# Top.net
KiCad netlist of a schematic drawn in Altium Designer
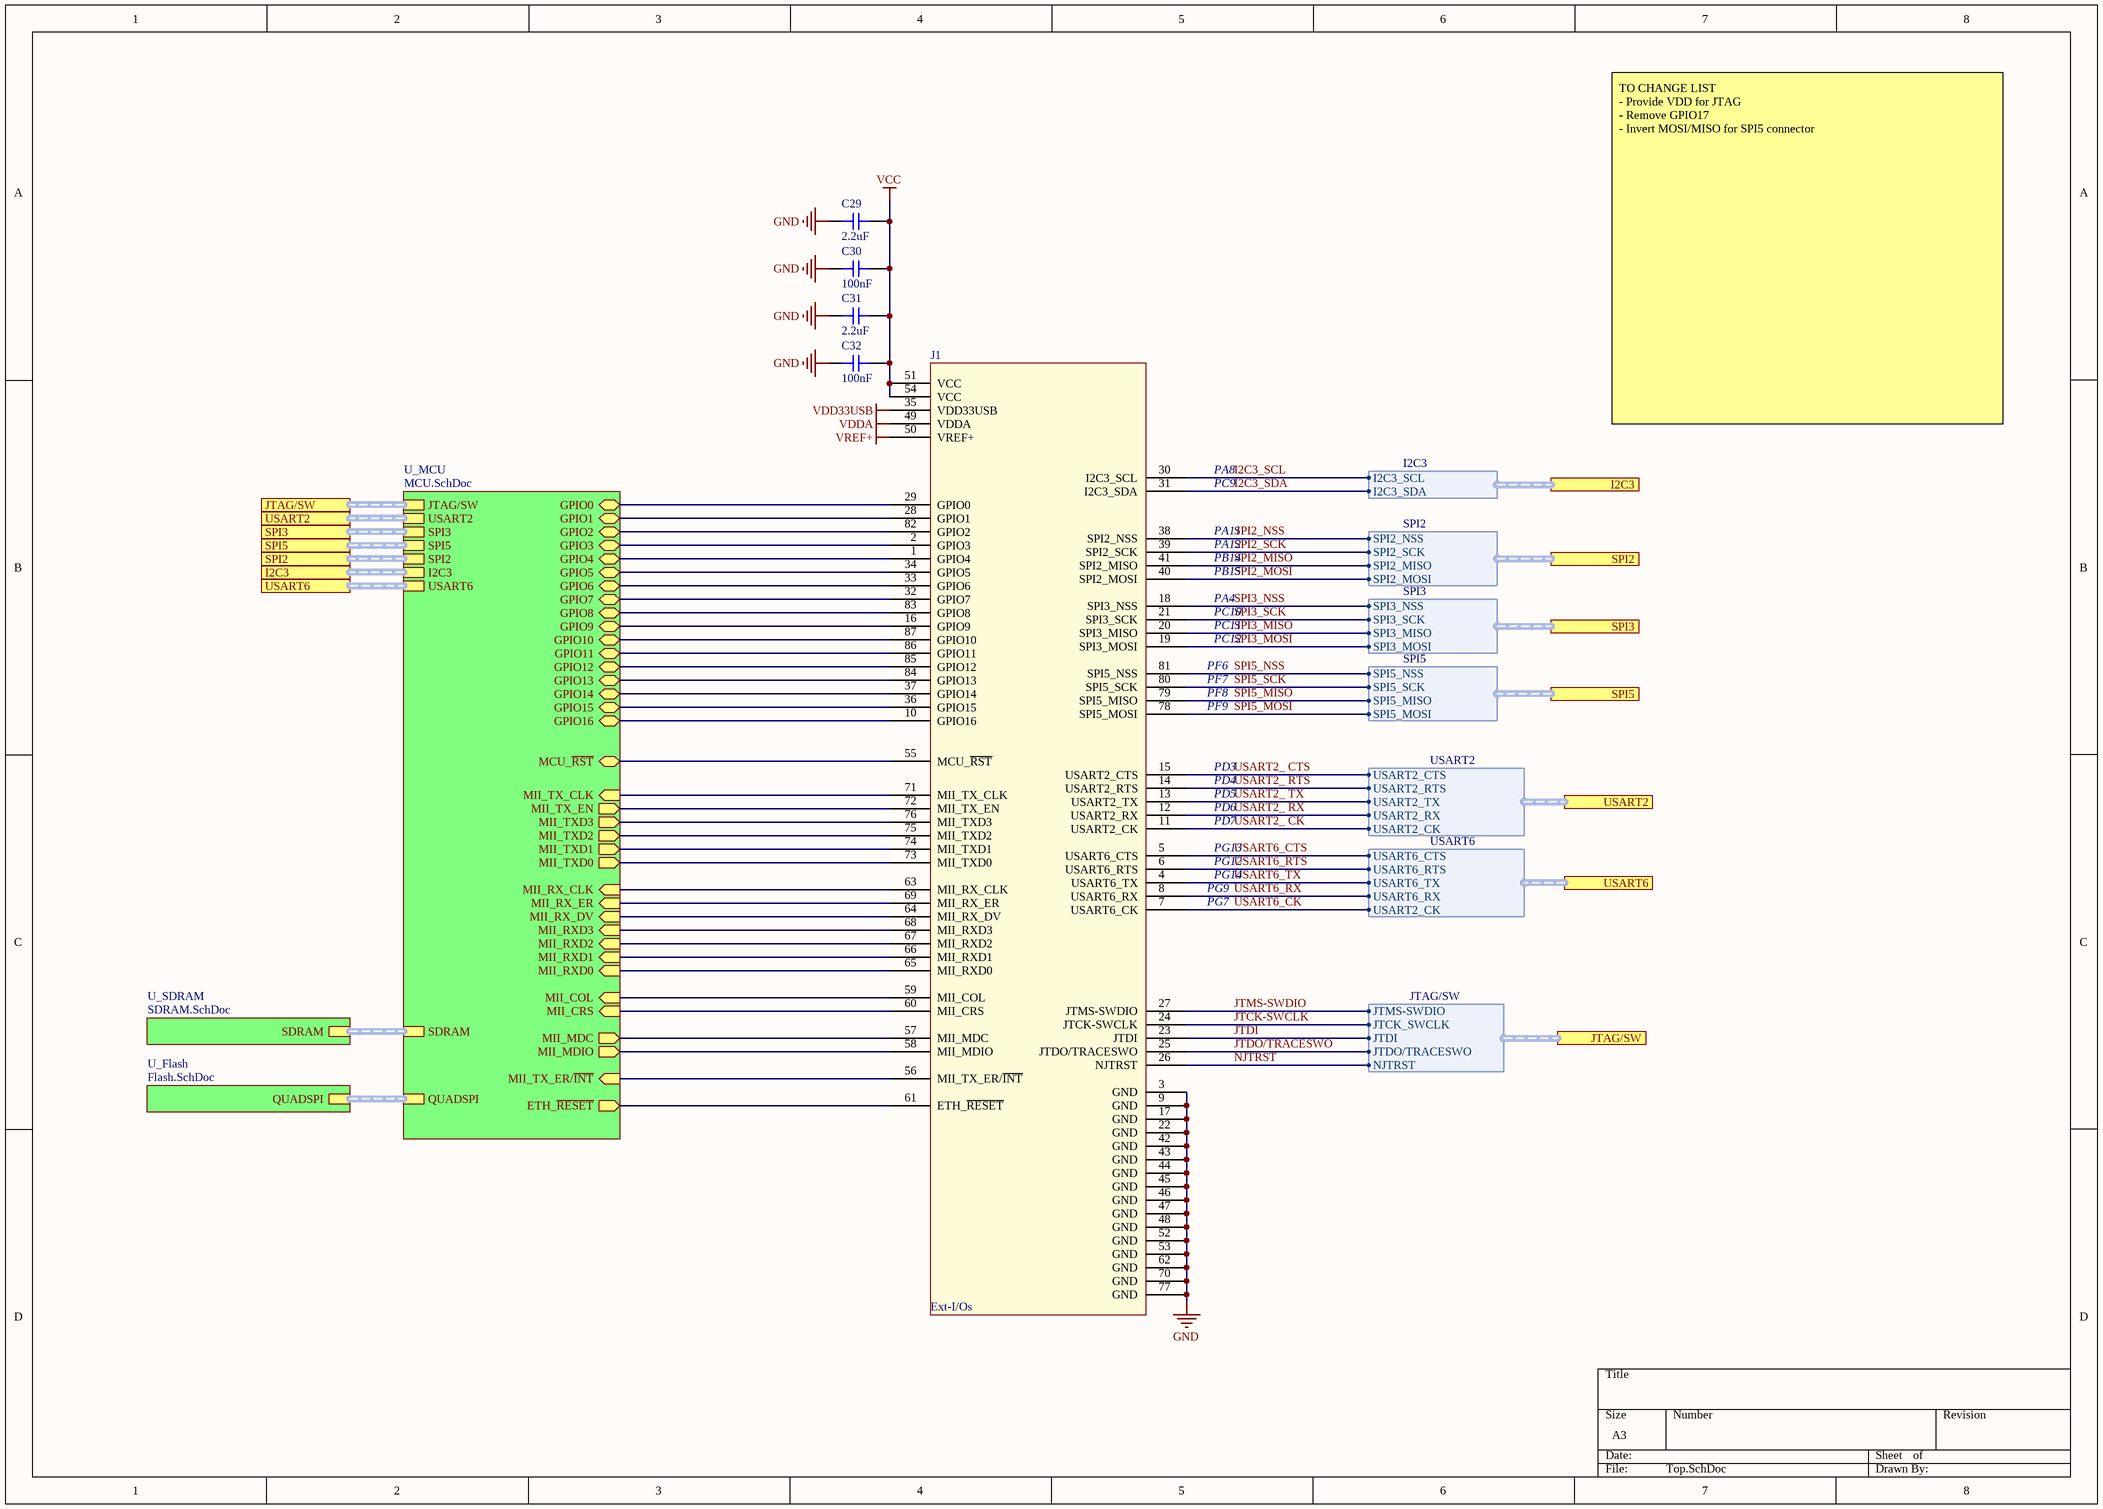
[diagram p0: Top.SchDoc]

(export (version "E")
  (design (tool "Eeschema 10.0.6"))
  (components
    (comp (ref "C29")
      (value "2.2uF")
      (footprint "Capacitor-0603")
      (fields (field (name "Comment") "C-2.2uF-0603"))
      (libsource (lib "Components") (part "C-2.2uF-0603"))
    )
    (comp (ref "C30")
      (value "100nF")
      (footprint "Capacitor-0603")
      (fields (field (name "Comment") "C-100nF-0603"))
      (libsource (lib "Components") (part "C-100nF-0603"))
    )
    (comp (ref "C31")
      (value "2.2uF")
      (footprint "Capacitor-0603")
      (fields (field (name "Comment") "C-2.2uF-0603"))
      (libsource (lib "Components") (part "C-2.2uF-0603"))
    )
    (comp (ref "C32")
      (value "100nF")
      (footprint "Capacitor-0603")
      (fields (field (name "Comment") "C-100nF-0603"))
      (libsource (lib "Components") (part "C-100nF-0603"))
    )
    (comp (ref "J1")
      (value "Ext-I/Os")
      (footprint "EXT_IOS")
      (libsource (lib "Components") (part "Ext-I/Os"))
    )
  )
  (nets
    (net (code "8") (name "/ETH_~{RESET}") (class "Default")
      (node (ref "J1") (pin "61") (pinfunction "ETH_~{RESET}_61") (pintype "passive"))
    )
    (net (code "9") (name "/GPIO0") (class "Default")
      (node (ref "J1") (pin "29") (pinfunction "GPIO0_29") (pintype "passive"))
    )
    (net (code "10") (name "/GPIO1") (class "Default")
      (node (ref "J1") (pin "28") (pinfunction "GPIO1_28") (pintype "passive"))
    )
    (net (code "11") (name "/GPIO2") (class "Default")
      (node (ref "J1") (pin "82") (pinfunction "GPIO2_82") (pintype "passive"))
    )
    (net (code "12") (name "/GPIO3") (class "Default")
      (node (ref "J1") (pin "2") (pinfunction "GPIO3_2") (pintype "passive"))
    )
    (net (code "13") (name "/GPIO4") (class "Default")
      (node (ref "J1") (pin "1") (pinfunction "GPIO4_1") (pintype "passive"))
    )
    (net (code "14") (name "/GPIO5") (class "Default")
      (node (ref "J1") (pin "34") (pinfunction "GPIO5_34") (pintype "passive"))
    )
    (net (code "15") (name "/GPIO6") (class "Default")
      (node (ref "J1") (pin "33") (pinfunction "GPIO6_33") (pintype "passive"))
    )
    (net (code "16") (name "/GPIO7") (class "Default")
      (node (ref "J1") (pin "32") (pinfunction "GPIO7_32") (pintype "passive"))
    )
    (net (code "17") (name "/GPIO8") (class "Default")
      (node (ref "J1") (pin "83") (pinfunction "GPIO8_83") (pintype "passive"))
    )
    (net (code "18") (name "/GPIO9") (class "Default")
      (node (ref "J1") (pin "16") (pinfunction "GPIO9_16") (pintype "passive"))
    )
    (net (code "19") (name "/GPIO10") (class "Default")
      (node (ref "J1") (pin "87") (pinfunction "GPIO10_87") (pintype "passive"))
    )
    (net (code "20") (name "/GPIO11") (class "Default")
      (node (ref "J1") (pin "86") (pinfunction "GPIO11_86") (pintype "passive"))
    )
    (net (code "21") (name "/GPIO12") (class "Default")
      (node (ref "J1") (pin "85") (pinfunction "GPIO12_85") (pintype "passive"))
    )
    (net (code "22") (name "/GPIO13") (class "Default")
      (node (ref "J1") (pin "84") (pinfunction "GPIO13_84") (pintype "passive"))
    )
    (net (code "23") (name "/GPIO14") (class "Default")
      (node (ref "J1") (pin "37") (pinfunction "GPIO14_37") (pintype "passive"))
    )
    (net (code "24") (name "/GPIO15") (class "Default")
      (node (ref "J1") (pin "36") (pinfunction "GPIO15_36") (pintype "passive"))
    )
    (net (code "25") (name "/GPIO16") (class "Default")
      (node (ref "J1") (pin "10") (pinfunction "GPIO16_10") (pintype "passive"))
    )
    (net (code "26") (name "/I2C3_SCL") (class "Default")
      (node (ref "J1") (pin "30") (pinfunction "I2C3_SCL_30") (pintype "passive"))
    )
    (net (code "27") (name "/I2C3_SDA") (class "Default")
      (node (ref "J1") (pin "31") (pinfunction "I2C3_SDA_31") (pintype "passive"))
    )
    (net (code "28") (name "/JTCK-SWCLK") (class "Default")
      (node (ref "J1") (pin "24") (pinfunction "JTCK-SWCLK_24") (pintype "passive"))
    )
    (net (code "29") (name "/JTDI") (class "Default")
      (node (ref "J1") (pin "23") (pinfunction "JTDI_23") (pintype "passive"))
    )
    (net (code "30") (name "/JTDO{slash}TRACESWO") (class "Default")
      (node (ref "J1") (pin "25") (pinfunction "JTDO/TRACESWO_25") (pintype "passive"))
    )
    (net (code "31") (name "/JTMS-SWDIO") (class "Default")
      (node (ref "J1") (pin "27") (pinfunction "JTMS-SWDIO_27") (pintype "passive"))
    )
    (net (code "32") (name "/MCU_~{RST}") (class "Default")
      (node (ref "J1") (pin "55") (pinfunction "MCU_~{RST}_55") (pintype "passive"))
    )
    (net (code "33") (name "/MII_COL") (class "Default")
      (node (ref "J1") (pin "59") (pinfunction "MII_COL_59") (pintype "passive"))
    )
    (net (code "34") (name "/MII_CRS") (class "Default")
      (node (ref "J1") (pin "60") (pinfunction "MII_CRS_60") (pintype "passive"))
    )
    (net (code "35") (name "/MII_MDC") (class "Default")
      (node (ref "J1") (pin "57") (pinfunction "MII_MDC_57") (pintype "passive"))
    )
    (net (code "36") (name "/MII_MDIO") (class "Default")
      (node (ref "J1") (pin "58") (pinfunction "MII_MDIO_58") (pintype "passive"))
    )
    (net (code "37") (name "/MII_RXD0") (class "Default")
      (node (ref "J1") (pin "65") (pinfunction "MII_RXD0_65") (pintype "passive"))
    )
    (net (code "38") (name "/MII_RXD1") (class "Default")
      (node (ref "J1") (pin "66") (pinfunction "MII_RXD1_66") (pintype "passive"))
    )
    (net (code "39") (name "/MII_RXD2") (class "Default")
      (node (ref "J1") (pin "67") (pinfunction "MII_RXD2_67") (pintype "passive"))
    )
    (net (code "40") (name "/MII_RXD3") (class "Default")
      (node (ref "J1") (pin "68") (pinfunction "MII_RXD3_68") (pintype "passive"))
    )
    (net (code "41") (name "/MII_RX_CLK") (class "Default")
      (node (ref "J1") (pin "63") (pinfunction "MII_RX_CLK_63") (pintype "passive"))
    )
    (net (code "42") (name "/MII_RX_DV") (class "Default")
      (node (ref "J1") (pin "64") (pinfunction "MII_RX_DV_64") (pintype "passive"))
    )
    (net (code "43") (name "/MII_RX_ER") (class "Default")
      (node (ref "J1") (pin "69") (pinfunction "MII_RX_ER_69") (pintype "passive"))
    )
    (net (code "44") (name "/MII_TXD0") (class "Default")
      (node (ref "J1") (pin "73") (pinfunction "MII_TXD0_73") (pintype "passive"))
    )
    (net (code "45") (name "/MII_TXD1") (class "Default")
      (node (ref "J1") (pin "74") (pinfunction "MII_TXD1_74") (pintype "passive"))
    )
    (net (code "46") (name "/MII_TXD2") (class "Default")
      (node (ref "J1") (pin "75") (pinfunction "MII_TXD2_75") (pintype "passive"))
    )
    (net (code "47") (name "/MII_TXD3") (class "Default")
      (node (ref "J1") (pin "76") (pinfunction "MII_TXD3_76") (pintype "passive"))
    )
    (net (code "48") (name "/MII_TX_CLK") (class "Default")
      (node (ref "J1") (pin "71") (pinfunction "MII_TX_CLK_71") (pintype "passive"))
    )
    (net (code "49") (name "/MII_TX_EN") (class "Default")
      (node (ref "J1") (pin "72") (pinfunction "MII_TX_EN_72") (pintype "passive"))
    )
    (net (code "50") (name "/MII_TX_ER{slash}~{INT}") (class "Default")
      (node (ref "J1") (pin "56") (pinfunction "MII_TX_ER/~{INT}_56") (pintype "passive"))
    )
    (net (code "51") (name "/NJTRST") (class "Default")
      (node (ref "J1") (pin "26") (pinfunction "NJTRST_26") (pintype "passive"))
    )
    (net (code "54") (name "/SPI2_MISO") (class "Default")
      (node (ref "J1") (pin "41") (pinfunction "SPI2_MISO_41") (pintype "passive"))
    )
    (net (code "55") (name "/SPI2_MOSI") (class "Default")
      (node (ref "J1") (pin "40") (pinfunction "SPI2_MOSI_40") (pintype "passive"))
    )
    (net (code "56") (name "/SPI2_NSS") (class "Default")
      (node (ref "J1") (pin "38") (pinfunction "SPI2_NSS_38") (pintype "passive"))
    )
    (net (code "57") (name "/SPI2_SCK") (class "Default")
      (node (ref "J1") (pin "39") (pinfunction "SPI2_SCK_39") (pintype "passive"))
    )
    (net (code "58") (name "/SPI3_MISO") (class "Default")
      (node (ref "J1") (pin "20") (pinfunction "SPI3_MISO_20") (pintype "passive"))
    )
    (net (code "59") (name "/SPI3_MOSI") (class "Default")
      (node (ref "J1") (pin "19") (pinfunction "SPI3_MOSI_19") (pintype "passive"))
    )
    (net (code "60") (name "/SPI3_NSS") (class "Default")
      (node (ref "J1") (pin "18") (pinfunction "SPI3_NSS_18") (pintype "passive"))
    )
    (net (code "61") (name "/SPI3_SCK") (class "Default")
      (node (ref "J1") (pin "21") (pinfunction "SPI3_SCK_21") (pintype "passive"))
    )
    (net (code "62") (name "/SPI5_MISO") (class "Default")
      (node (ref "J1") (pin "79") (pinfunction "SPI5_MISO_79") (pintype "passive"))
    )
    (net (code "63") (name "/SPI5_MOSI") (class "Default")
      (node (ref "J1") (pin "78") (pinfunction "SPI5_MOSI_78") (pintype "passive"))
    )
    (net (code "64") (name "/SPI5_NSS") (class "Default")
      (node (ref "J1") (pin "81") (pinfunction "SPI5_NSS_81") (pintype "passive"))
    )
    (net (code "65") (name "/SPI5_SCK") (class "Default")
      (node (ref "J1") (pin "80") (pinfunction "SPI5_SCK_80") (pintype "passive"))
    )
    (net (code "66") (name "/USART2_ CK") (class "Default")
      (node (ref "J1") (pin "11") (pinfunction "USART2_CK_11") (pintype "passive"))
    )
    (net (code "67") (name "/USART2_ CTS") (class "Default")
      (node (ref "J1") (pin "15") (pinfunction "USART2_CTS_15") (pintype "passive"))
    )
    (net (code "68") (name "/USART2_ RTS") (class "Default")
      (node (ref "J1") (pin "14") (pinfunction "USART2_RTS_14") (pintype "passive"))
    )
    (net (code "69") (name "/USART2_ RX") (class "Default")
      (node (ref "J1") (pin "12") (pinfunction "USART2_RX_12") (pintype "passive"))
    )
    (net (code "70") (name "/USART2_ TX") (class "Default")
      (node (ref "J1") (pin "13") (pinfunction "USART2_TX_13") (pintype "passive"))
    )
    (net (code "71") (name "/USART6_CK") (class "Default")
      (node (ref "J1") (pin "7") (pinfunction "USART6_CK_7") (pintype "passive"))
    )
    (net (code "72") (name "/USART6_CTS") (class "Default")
      (node (ref "J1") (pin "5") (pinfunction "USART6_CTS_5") (pintype "passive"))
    )
    (net (code "73") (name "/USART6_RTS") (class "Default")
      (node (ref "J1") (pin "6") (pinfunction "USART6_RTS_6") (pintype "passive"))
    )
    (net (code "74") (name "/USART6_RX") (class "Default")
      (node (ref "J1") (pin "8") (pinfunction "USART6_RX_8") (pintype "passive"))
    )
    (net (code "75") (name "/USART6_TX") (class "Default")
      (node (ref "J1") (pin "4") (pinfunction "USART6_TX_4") (pintype "passive"))
    )
    (net (code "83") (name "GND") (class "Default")
      (node (ref "C29") (pin "1") (pinfunction "1_1") (pintype "passive"))
      (node (ref "C30") (pin "1") (pinfunction "1_1") (pintype "passive"))
      (node (ref "C31") (pin "1") (pinfunction "1_1") (pintype "passive"))
      (node (ref "C32") (pin "1") (pinfunction "1_1") (pintype "passive"))
      (node (ref "J1") (pin "17") (pinfunction "GND_17") (pintype "passive"))
      (node (ref "J1") (pin "22") (pinfunction "GND_22") (pintype "passive"))
      (node (ref "J1") (pin "3") (pinfunction "GND_3") (pintype "passive"))
      (node (ref "J1") (pin "42") (pinfunction "GND_42") (pintype "passive"))
      (node (ref "J1") (pin "43") (pinfunction "GND_43") (pintype "passive"))
      (node (ref "J1") (pin "44") (pinfunction "GND_44") (pintype "passive"))
      (node (ref "J1") (pin "45") (pinfunction "GND_45") (pintype "passive"))
      (node (ref "J1") (pin "46") (pinfunction "GND_46") (pintype "passive"))
      (node (ref "J1") (pin "47") (pinfunction "GND_47") (pintype "passive"))
      (node (ref "J1") (pin "48") (pinfunction "GND_48") (pintype "passive"))
      (node (ref "J1") (pin "52") (pinfunction "GND_52") (pintype "passive"))
      (node (ref "J1") (pin "53") (pinfunction "GND_53") (pintype "passive"))
      (node (ref "J1") (pin "62") (pinfunction "GND_62") (pintype "passive"))
      (node (ref "J1") (pin "70") (pinfunction "GND_70") (pintype "passive"))
      (node (ref "J1") (pin "77") (pinfunction "GND_77") (pintype "passive"))
      (node (ref "J1") (pin "9") (pinfunction "GND_9") (pintype "passive"))
    )
    (net (code "84") (name "VCC") (class "Default")
      (node (ref "C29") (pin "2") (pinfunction "2_2") (pintype "passive"))
      (node (ref "C30") (pin "2") (pinfunction "2_2") (pintype "passive"))
      (node (ref "C31") (pin "2") (pinfunction "2_2") (pintype "passive"))
      (node (ref "C32") (pin "2") (pinfunction "2_2") (pintype "passive"))
      (node (ref "J1") (pin "51") (pinfunction "VCC_51") (pintype "passive"))
      (node (ref "J1") (pin "54") (pinfunction "VCC_54") (pintype "passive"))
    )
    (net (code "85") (name "VDD33USB") (class "Default")
      (node (ref "J1") (pin "35") (pinfunction "VDD33USB_35") (pintype "passive"))
    )
    (net (code "86") (name "VDDA") (class "Default")
      (node (ref "J1") (pin "49") (pinfunction "VDDA_49") (pintype "passive"))
    )
    (net (code "87") (name "VREF+") (class "Default")
      (node (ref "J1") (pin "50") (pinfunction "VREF+_50") (pintype "passive"))
    )
  )
)
